# USB_breakout.net
KiCad netlist of a schematic drawn in EAGLE
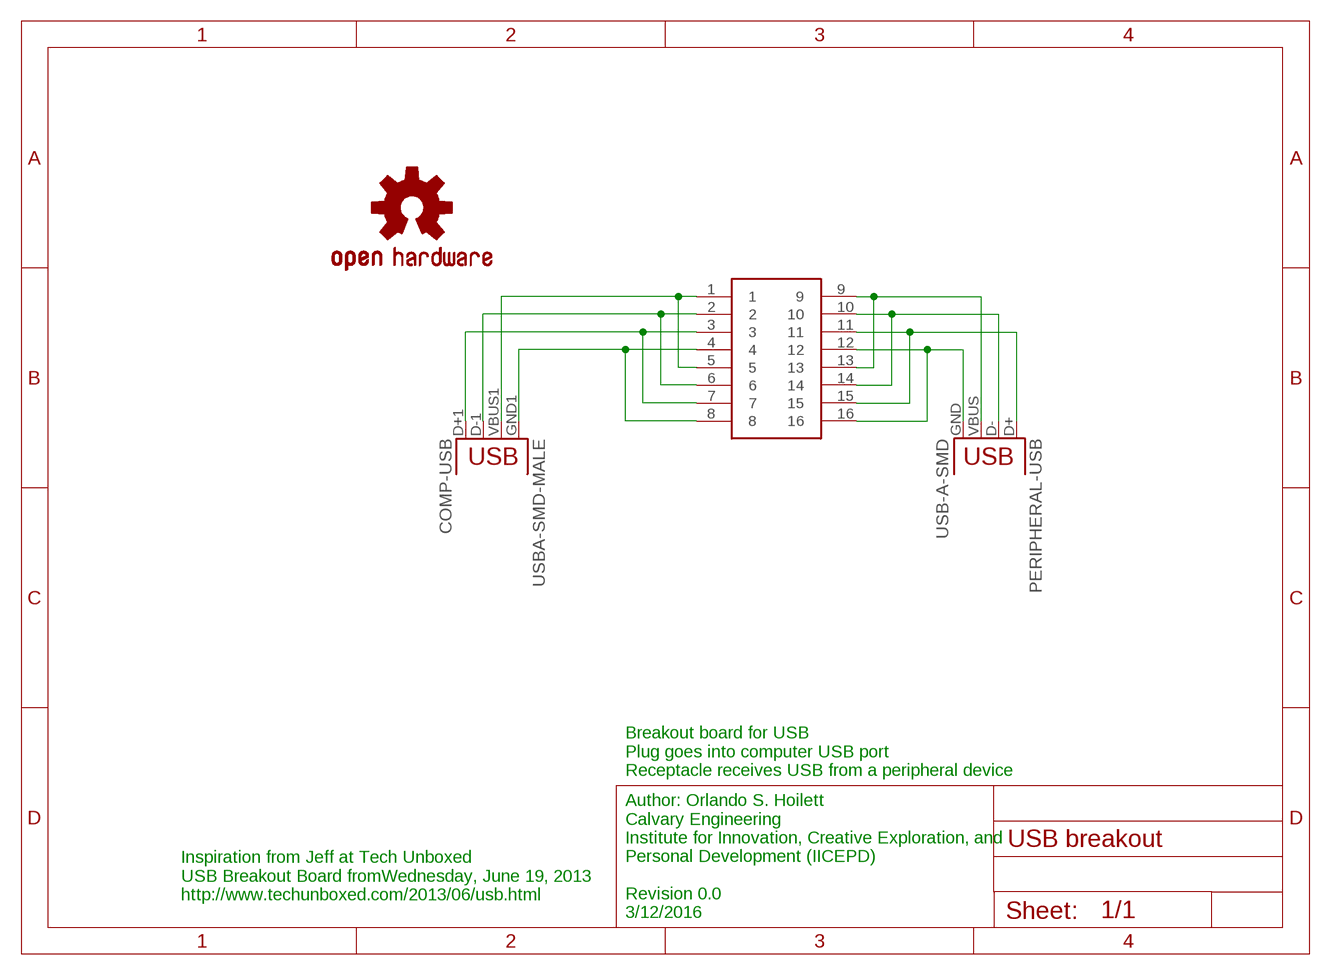
[diagram p0: schematic, sheet 1]

(export (version "E")
  (design (tool "Eeschema 10.0.6"))
  (components
    (comp (ref "COMP-USB")
      (value "USBA-SMD-MALE")
      (footprint "eagle-import:USB-A-SMT-MALE")
      (libsource (lib "eagle-import") (part "USBA-SMD-MALE"))
    )
    (comp (ref "LOGO1")
      (value "OSHW-LOGOS")
      (footprint "eagle-import:OSHW-LOGO-S")
      (libsource (lib "eagle-import") (part "OSHW-LOGOS"))
    )
    (comp (ref "PERIPHERAL-USB")
      (value "USB-A-SMD")
      (footprint "eagle-import:USB-A-S-NOSILK-FEMALE")
      (libsource (lib "eagle-import") (part "USB-A-SMD"))
    )
    (comp (ref "U$1")
      (value "MX4X4")
      (footprint "eagle-import:M04X4")
      (libsource (lib "eagle-import") (part "MX4X4"))
    )
  )
  (nets
    (net (code "1") (name "Net-(COMP-USB-D+)") (class "Default")
      (node (ref "COMP-USB") (pin "D+1") (pinfunction "D+_D+1") (pintype "bidirectional"))
      (node (ref "U$1") (pin "3") (pinfunction "3_3") (pintype "bidirectional"))
      (node (ref "U$1") (pin "7") (pinfunction "7_7") (pintype "bidirectional"))
    )
    (net (code "2") (name "Net-(COMP-USB-D-)") (class "Default")
      (node (ref "COMP-USB") (pin "D-1") (pinfunction "D-_D-1") (pintype "bidirectional"))
      (node (ref "U$1") (pin "2") (pinfunction "2_2") (pintype "bidirectional"))
      (node (ref "U$1") (pin "6") (pinfunction "6_6") (pintype "bidirectional"))
    )
    (net (code "3") (name "Net-(COMP-USB-GND)") (class "Default")
      (node (ref "COMP-USB") (pin "GND1") (pinfunction "GND_GND1") (pintype "bidirectional"))
      (node (ref "U$1") (pin "4") (pinfunction "4_4") (pintype "bidirectional"))
      (node (ref "U$1") (pin "8") (pinfunction "8_8") (pintype "bidirectional"))
    )
    (net (code "4") (name "Net-(COMP-USB-VBUS)") (class "Default")
      (node (ref "COMP-USB") (pin "VBUS1") (pinfunction "VBUS_VBUS1") (pintype "bidirectional"))
      (node (ref "U$1") (pin "1") (pinfunction "1_1") (pintype "bidirectional"))
      (node (ref "U$1") (pin "5") (pinfunction "5_5") (pintype "bidirectional"))
    )
    (net (code "5") (name "Net-(PERIPHERAL-USB-PadD+)") (class "Default")
      (node (ref "PERIPHERAL-USB") (pin "D+") (pinfunction "D+_D+") (pintype "bidirectional"))
      (node (ref "U$1") (pin "11") (pinfunction "11_11") (pintype "bidirectional"))
      (node (ref "U$1") (pin "15") (pinfunction "15_15") (pintype "bidirectional"))
    )
    (net (code "6") (name "Net-(PERIPHERAL-USB-PadD-)") (class "Default")
      (node (ref "PERIPHERAL-USB") (pin "D-") (pinfunction "D-_D-") (pintype "bidirectional"))
      (node (ref "U$1") (pin "10") (pinfunction "10_10") (pintype "bidirectional"))
      (node (ref "U$1") (pin "14") (pinfunction "14_14") (pintype "bidirectional"))
    )
    (net (code "7") (name "Net-(PERIPHERAL-USB-PadGND)") (class "Default")
      (node (ref "PERIPHERAL-USB") (pin "GND") (pinfunction "GND_GND") (pintype "bidirectional"))
      (node (ref "U$1") (pin "12") (pinfunction "12_12") (pintype "bidirectional"))
      (node (ref "U$1") (pin "16") (pinfunction "16_16") (pintype "bidirectional"))
    )
    (net (code "8") (name "Net-(PERIPHERAL-USB-PadVBUS)") (class "Default")
      (node (ref "PERIPHERAL-USB") (pin "VBUS") (pinfunction "VBUS_VBUS") (pintype "bidirectional"))
      (node (ref "U$1") (pin "13") (pinfunction "13_13") (pintype "bidirectional"))
      (node (ref "U$1") (pin "9") (pinfunction "9_9") (pintype "bidirectional"))
    )
  )
)
